# output.net
KiCad netlist of a schematic drawn in Altium Designer
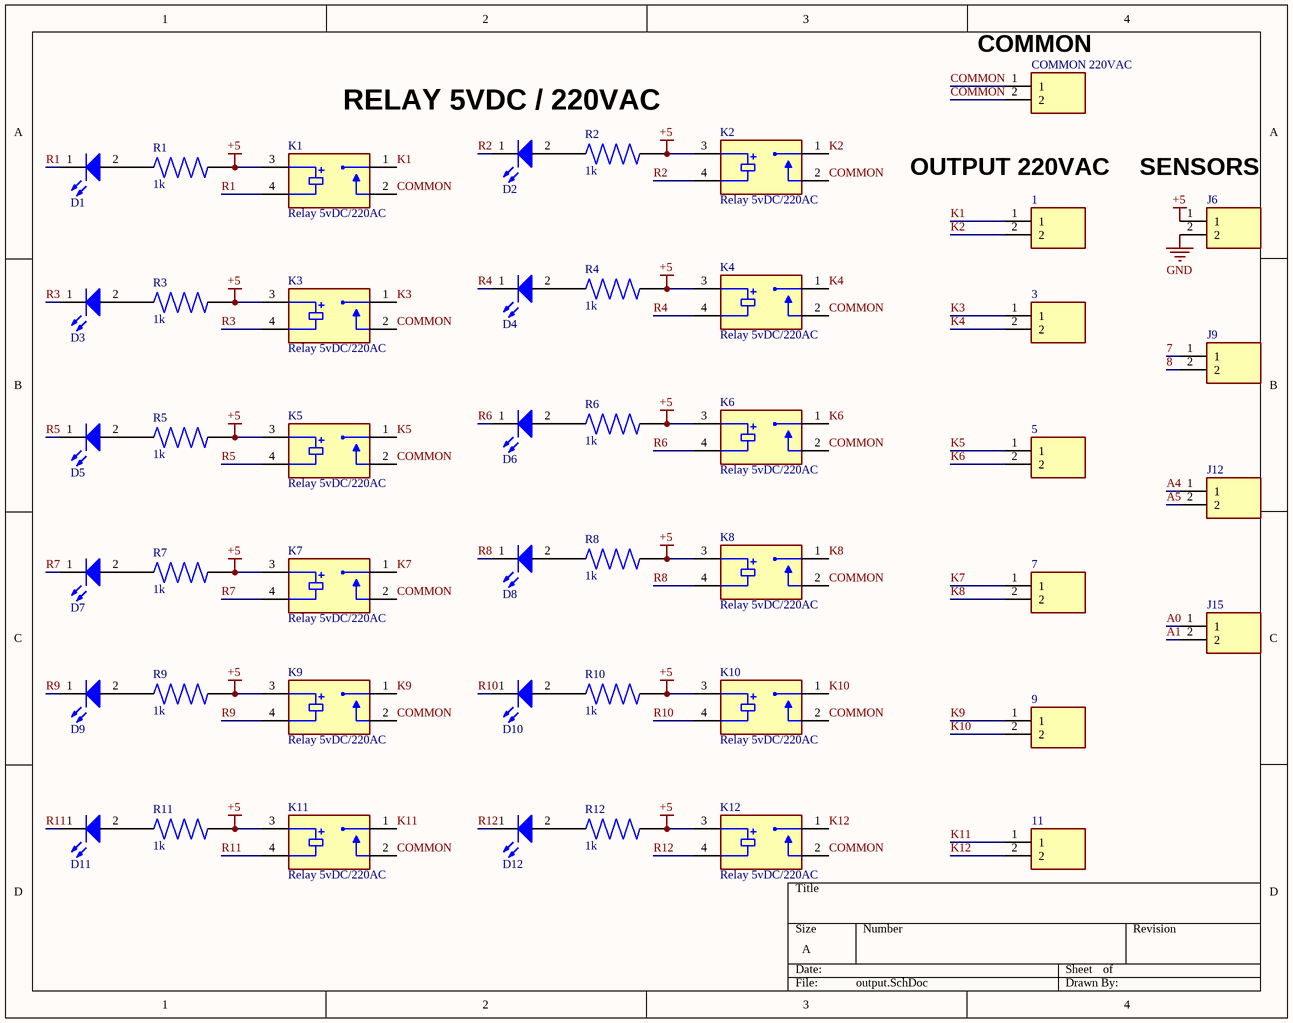
[diagram p0: output.SchDoc]

(export (version "E")
  (design (tool "Eeschema 10.0.6"))
  (components
    (comp (ref "1")
      (value "282856-2")
      (footprint "TE_282856-2")
      (description "TERMI-BLOK PCB MOUNT 2P")
      (fields (field (name "MF") "TE Connectivity"))
      (libsource (lib "input") (part "282856-2"))
    )
    (comp (ref "3")
      (value "282856-2")
      (footprint "TE_282856-2")
      (description "TERMI-BLOK PCB MOUNT 2P")
      (fields (field (name "MF") "TE Connectivity"))
      (libsource (lib "input") (part "282856-2"))
    )
    (comp (ref "5")
      (value "282856-2")
      (footprint "TE_282856-2")
      (description "TERMI-BLOK PCB MOUNT 2P")
      (fields (field (name "MF") "TE Connectivity"))
      (libsource (lib "input") (part "282856-2"))
    )
    (comp (ref "7")
      (value "282856-2")
      (footprint "TE_282856-2")
      (description "TERMI-BLOK PCB MOUNT 2P")
      (fields (field (name "MF") "TE Connectivity"))
      (libsource (lib "input") (part "282856-2"))
    )
    (comp (ref "9")
      (value "282856-2")
      (footprint "TE_282856-2")
      (description "TERMI-BLOK PCB MOUNT 2P")
      (fields (field (name "MF") "TE Connectivity"))
      (libsource (lib "input") (part "282856-2"))
    )
    (comp (ref "11")
      (value "282856-2")
      (footprint "TE_282856-2")
      (description "TERMI-BLOK PCB MOUNT 2P")
      (fields (field (name "MF") "TE Connectivity"))
      (libsource (lib "input") (part "282856-2"))
    )
    (comp (ref "COMMON 220VAC")
      (value "282856-2")
      (footprint "TE_282856-2")
      (description "TERMI-BLOK PCB MOUNT 2P")
      (fields (field (name "MF") "TE Connectivity"))
      (libsource (lib "input") (part "282856-2"))
    )
    (comp (ref "D1")
      (value "Infrared, 1.4V, 140°")
      (footprint "WL-SICW_0805_L2W1.3H0.8")
      (description "WL-SICW SMT Chip LED Infrared Waterclear, size 1206, Infrared, 1.4V, 140°")
      (fields
        (field (name "MANUFACTURER PART NUMBER") "15412085BA400")
        (field (name "MANUFACTURER") "Wurth Elektronik")
      )
      (libsource (lib "input") (part "15412085BA400"))
    )
    (comp (ref "D2")
      (value "Infrared, 1.4V, 140°")
      (footprint "WL-SICW_0805_L2W1.3H0.8")
      (description "WL-SICW SMT Chip LED Infrared Waterclear, size 1206, Infrared, 1.4V, 140°")
      (fields
        (field (name "MANUFACTURER PART NUMBER") "15412085BA400")
        (field (name "MANUFACTURER") "Wurth Elektronik")
      )
      (libsource (lib "input") (part "15412085BA400"))
    )
    (comp (ref "D3")
      (value "Infrared, 1.4V, 140°")
      (footprint "WL-SICW_0805_L2W1.3H0.8")
      (description "WL-SICW SMT Chip LED Infrared Waterclear, size 1206, Infrared, 1.4V, 140°")
      (fields
        (field (name "MANUFACTURER PART NUMBER") "15412085BA400")
        (field (name "MANUFACTURER") "Wurth Elektronik")
      )
      (libsource (lib "input") (part "15412085BA400"))
    )
    (comp (ref "D4")
      (value "Infrared, 1.4V, 140°")
      (footprint "WL-SICW_0805_L2W1.3H0.8")
      (description "WL-SICW SMT Chip LED Infrared Waterclear, size 1206, Infrared, 1.4V, 140°")
      (fields
        (field (name "MANUFACTURER PART NUMBER") "15412085BA400")
        (field (name "MANUFACTURER") "Wurth Elektronik")
      )
      (libsource (lib "input") (part "15412085BA400"))
    )
    (comp (ref "D5")
      (value "Infrared, 1.4V, 140°")
      (footprint "WL-SICW_0805_L2W1.3H0.8")
      (description "WL-SICW SMT Chip LED Infrared Waterclear, size 1206, Infrared, 1.4V, 140°")
      (fields
        (field (name "MANUFACTURER PART NUMBER") "15412085BA400")
        (field (name "MANUFACTURER") "Wurth Elektronik")
      )
      (libsource (lib "input") (part "15412085BA400"))
    )
    (comp (ref "D6")
      (value "Infrared, 1.4V, 140°")
      (footprint "WL-SICW_0805_L2W1.3H0.8")
      (description "WL-SICW SMT Chip LED Infrared Waterclear, size 1206, Infrared, 1.4V, 140°")
      (fields
        (field (name "MANUFACTURER PART NUMBER") "15412085BA400")
        (field (name "MANUFACTURER") "Wurth Elektronik")
      )
      (libsource (lib "input") (part "15412085BA400"))
    )
    (comp (ref "D7")
      (value "Infrared, 1.4V, 140°")
      (footprint "WL-SICW_0805_L2W1.3H0.8")
      (description "WL-SICW SMT Chip LED Infrared Waterclear, size 1206, Infrared, 1.4V, 140°")
      (fields
        (field (name "MANUFACTURER PART NUMBER") "15412085BA400")
        (field (name "MANUFACTURER") "Wurth Elektronik")
      )
      (libsource (lib "input") (part "15412085BA400"))
    )
    (comp (ref "D8")
      (value "Infrared, 1.4V, 140°")
      (footprint "WL-SICW_0805_L2W1.3H0.8")
      (description "WL-SICW SMT Chip LED Infrared Waterclear, size 1206, Infrared, 1.4V, 140°")
      (fields
        (field (name "MANUFACTURER PART NUMBER") "15412085BA400")
        (field (name "MANUFACTURER") "Wurth Elektronik")
      )
      (libsource (lib "input") (part "15412085BA400"))
    )
    (comp (ref "D9")
      (value "Infrared, 1.4V, 140°")
      (footprint "WL-SICW_0805_L2W1.3H0.8")
      (description "WL-SICW SMT Chip LED Infrared Waterclear, size 1206, Infrared, 1.4V, 140°")
      (fields
        (field (name "MANUFACTURER PART NUMBER") "15412085BA400")
        (field (name "MANUFACTURER") "Wurth Elektronik")
      )
      (libsource (lib "input") (part "15412085BA400"))
    )
    (comp (ref "D10")
      (value "Infrared, 1.4V, 140°")
      (footprint "WL-SICW_0805_L2W1.3H0.8")
      (description "WL-SICW SMT Chip LED Infrared Waterclear, size 1206, Infrared, 1.4V, 140°")
      (fields
        (field (name "MANUFACTURER PART NUMBER") "15412085BA400")
        (field (name "MANUFACTURER") "Wurth Elektronik")
      )
      (libsource (lib "input") (part "15412085BA400"))
    )
    (comp (ref "D11")
      (value "Infrared, 1.4V, 140°")
      (footprint "WL-SICW_0805_L2W1.3H0.8")
      (description "WL-SICW SMT Chip LED Infrared Waterclear, size 1206, Infrared, 1.4V, 140°")
      (fields
        (field (name "MANUFACTURER PART NUMBER") "15412085BA400")
        (field (name "MANUFACTURER") "Wurth Elektronik")
      )
      (libsource (lib "input") (part "15412085BA400"))
    )
    (comp (ref "D12")
      (value "Infrared, 1.4V, 140°")
      (footprint "WL-SICW_0805_L2W1.3H0.8")
      (description "WL-SICW SMT Chip LED Infrared Waterclear, size 1206, Infrared, 1.4V, 140°")
      (fields
        (field (name "MANUFACTURER PART NUMBER") "15412085BA400")
        (field (name "MANUFACTURER") "Wurth Elektronik")
      )
      (libsource (lib "input") (part "15412085BA400"))
    )
    (comp (ref "J6")
      (value "282856-2")
      (footprint "TE_282856-2")
      (description "TERMI-BLOK PCB MOUNT 2P")
      (fields (field (name "MF") "TE Connectivity"))
      (libsource (lib "input") (part "282856-2"))
    )
    (comp (ref "J9")
      (value "282856-2")
      (footprint "TE_282856-2")
      (description "TERMI-BLOK PCB MOUNT 2P")
      (fields (field (name "MF") "TE Connectivity"))
      (libsource (lib "input") (part "282856-2"))
    )
    (comp (ref "J12")
      (value "282856-2")
      (footprint "TE_282856-2")
      (description "TERMI-BLOK PCB MOUNT 2P")
      (fields (field (name "MF") "TE Connectivity"))
      (libsource (lib "input") (part "282856-2"))
    )
    (comp (ref "J15")
      (value "282856-2")
      (footprint "TE_282856-2")
      (description "TERMI-BLOK PCB MOUNT 2P")
      (fields (field (name "MF") "TE Connectivity"))
      (libsource (lib "input") (part "282856-2"))
    )
    (comp (ref "K1")
      (value "Relay 5vDC/220AC")
      (footprint "control:RELAY_G3MB-202PDC5")
      (description "Solid State SPST-NO (1 Form A) 4-SIP")
      (fields (field (name "MP") "G3MB-202P DC5") (field (name "MF") "Omron Automation"))
      (libsource (lib "control") (part "G3MB-202PDC5"))
    )
    (comp (ref "K2")
      (value "Relay 5vDC/220AC")
      (footprint "control:RELAY_G3MB-202PDC5")
      (description "Solid State SPST-NO (1 Form A) 4-SIP")
      (fields (field (name "MP") "G3MB-202P DC5") (field (name "MF") "Omron Automation"))
      (libsource (lib "control") (part "G3MB-202PDC5"))
    )
    (comp (ref "K3")
      (value "Relay 5vDC/220AC")
      (footprint "control:RELAY_G3MB-202PDC5")
      (description "Solid State SPST-NO (1 Form A) 4-SIP")
      (fields (field (name "MP") "G3MB-202P DC5") (field (name "MF") "Omron Automation"))
      (libsource (lib "control") (part "G3MB-202PDC5"))
    )
    (comp (ref "K4")
      (value "Relay 5vDC/220AC")
      (footprint "control:RELAY_G3MB-202PDC5")
      (description "Solid State SPST-NO (1 Form A) 4-SIP")
      (fields (field (name "MP") "G3MB-202P DC5") (field (name "MF") "Omron Automation"))
      (libsource (lib "control") (part "G3MB-202PDC5"))
    )
    (comp (ref "K5")
      (value "Relay 5vDC/220AC")
      (footprint "control:RELAY_G3MB-202PDC5")
      (description "Solid State SPST-NO (1 Form A) 4-SIP")
      (fields (field (name "MP") "G3MB-202P DC5") (field (name "MF") "Omron Automation"))
      (libsource (lib "control") (part "G3MB-202PDC5"))
    )
    (comp (ref "K6")
      (value "Relay 5vDC/220AC")
      (footprint "control:RELAY_G3MB-202PDC5")
      (description "Solid State SPST-NO (1 Form A) 4-SIP")
      (fields (field (name "MP") "G3MB-202P DC5") (field (name "MF") "Omron Automation"))
      (libsource (lib "control") (part "G3MB-202PDC5"))
    )
    (comp (ref "K7")
      (value "Relay 5vDC/220AC")
      (footprint "control:RELAY_G3MB-202PDC5")
      (description "Solid State SPST-NO (1 Form A) 4-SIP")
      (fields (field (name "MP") "G3MB-202P DC5") (field (name "MF") "Omron Automation"))
      (libsource (lib "control") (part "G3MB-202PDC5"))
    )
    (comp (ref "K8")
      (value "Relay 5vDC/220AC")
      (footprint "control:RELAY_G3MB-202PDC5")
      (description "Solid State SPST-NO (1 Form A) 4-SIP")
      (fields (field (name "MP") "G3MB-202P DC5") (field (name "MF") "Omron Automation"))
      (libsource (lib "control") (part "G3MB-202PDC5"))
    )
    (comp (ref "K9")
      (value "Relay 5vDC/220AC")
      (footprint "control:RELAY_G3MB-202PDC5")
      (description "Solid State SPST-NO (1 Form A) 4-SIP")
      (fields (field (name "MP") "G3MB-202P DC5") (field (name "MF") "Omron Automation"))
      (libsource (lib "control") (part "G3MB-202PDC5"))
    )
    (comp (ref "K10")
      (value "Relay 5vDC/220AC")
      (footprint "control:RELAY_G3MB-202PDC5")
      (description "Solid State SPST-NO (1 Form A) 4-SIP")
      (fields (field (name "MP") "G3MB-202P DC5") (field (name "MF") "Omron Automation"))
      (libsource (lib "control") (part "G3MB-202PDC5"))
    )
    (comp (ref "K11")
      (value "Relay 5vDC/220AC")
      (footprint "control:RELAY_G3MB-202PDC5")
      (description "Solid State SPST-NO (1 Form A) 4-SIP")
      (fields (field (name "MP") "G3MB-202P DC5") (field (name "MF") "Omron Automation"))
      (libsource (lib "control") (part "G3MB-202PDC5"))
    )
    (comp (ref "K12")
      (value "Relay 5vDC/220AC")
      (footprint "control:RELAY_G3MB-202PDC5")
      (description "Solid State SPST-NO (1 Form A) 4-SIP")
      (fields (field (name "MP") "G3MB-202P DC5") (field (name "MF") "Omron Automation"))
      (libsource (lib "control") (part "G3MB-202PDC5"))
    )
    (comp (ref "R1")
      (value "1k")
      (footprint "RESC3216X70N")
      (description "Res 1206 10 Ohm 5% 1/8W Â±500ppm/Â°C Molded SMD SMD T/R")
      (fields (field (name "TOLERANCE") "5%") (field (name "MP") "FCR1206J10R"))
      (libsource (lib "input") (part "FCR1206J10R"))
    )
    (comp (ref "R2")
      (value "1k")
      (footprint "RESC3216X70N")
      (description "Res 1206 10 Ohm 5% 1/8W Â±500ppm/Â°C Molded SMD SMD T/R")
      (fields (field (name "TOLERANCE") "5%") (field (name "MP") "FCR1206J10R"))
      (libsource (lib "input") (part "FCR1206J10R"))
    )
    (comp (ref "R3")
      (value "1k")
      (footprint "RESC3216X70N")
      (description "Res 1206 10 Ohm 5% 1/8W Â±500ppm/Â°C Molded SMD SMD T/R")
      (fields (field (name "TOLERANCE") "5%") (field (name "MP") "FCR1206J10R"))
      (libsource (lib "input") (part "FCR1206J10R"))
    )
    (comp (ref "R4")
      (value "1k")
      (footprint "RESC3216X70N")
      (description "Res 1206 10 Ohm 5% 1/8W Â±500ppm/Â°C Molded SMD SMD T/R")
      (fields (field (name "TOLERANCE") "5%") (field (name "MP") "FCR1206J10R"))
      (libsource (lib "input") (part "FCR1206J10R"))
    )
    (comp (ref "R5")
      (value "1k")
      (footprint "RESC3216X70N")
      (description "Res 1206 10 Ohm 5% 1/8W Â±500ppm/Â°C Molded SMD SMD T/R")
      (fields (field (name "TOLERANCE") "5%") (field (name "MP") "FCR1206J10R"))
      (libsource (lib "input") (part "FCR1206J10R"))
    )
    (comp (ref "R6")
      (value "1k")
      (footprint "RESC3216X70N")
      (description "Res 1206 10 Ohm 5% 1/8W Â±500ppm/Â°C Molded SMD SMD T/R")
      (fields (field (name "TOLERANCE") "5%") (field (name "MP") "FCR1206J10R"))
      (libsource (lib "input") (part "FCR1206J10R"))
    )
    (comp (ref "R7")
      (value "1k")
      (footprint "RESC3216X70N")
      (description "Res 1206 10 Ohm 5% 1/8W Â±500ppm/Â°C Molded SMD SMD T/R")
      (fields (field (name "TOLERANCE") "5%") (field (name "MP") "FCR1206J10R"))
      (libsource (lib "input") (part "FCR1206J10R"))
    )
    (comp (ref "R8")
      (value "1k")
      (footprint "RESC3216X70N")
      (description "Res 1206 10 Ohm 5% 1/8W Â±500ppm/Â°C Molded SMD SMD T/R")
      (fields (field (name "TOLERANCE") "5%") (field (name "MP") "FCR1206J10R"))
      (libsource (lib "input") (part "FCR1206J10R"))
    )
    (comp (ref "R9")
      (value "1k")
      (footprint "RESC3216X70N")
      (description "Res 1206 10 Ohm 5% 1/8W Â±500ppm/Â°C Molded SMD SMD T/R")
      (fields (field (name "TOLERANCE") "5%") (field (name "MP") "FCR1206J10R"))
      (libsource (lib "input") (part "FCR1206J10R"))
    )
    (comp (ref "R10")
      (value "1k")
      (footprint "RESC3216X70N")
      (description "Res 1206 10 Ohm 5% 1/8W Â±500ppm/Â°C Molded SMD SMD T/R")
      (fields (field (name "TOLERANCE") "5%") (field (name "MP") "FCR1206J10R"))
      (libsource (lib "input") (part "FCR1206J10R"))
    )
    (comp (ref "R11")
      (value "1k")
      (footprint "RESC3216X70N")
      (description "Res 1206 10 Ohm 5% 1/8W Â±500ppm/Â°C Molded SMD SMD T/R")
      (fields (field (name "TOLERANCE") "5%") (field (name "MP") "FCR1206J10R"))
      (libsource (lib "input") (part "FCR1206J10R"))
    )
    (comp (ref "R12")
      (value "1k")
      (footprint "RESC3216X70N")
      (description "Res 1206 10 Ohm 5% 1/8W Â±500ppm/Â°C Molded SMD SMD T/R")
      (fields (field (name "TOLERANCE") "5%") (field (name "MP") "FCR1206J10R"))
      (libsource (lib "input") (part "FCR1206J10R"))
    )
  )
  (nets
    (net (code "1") (name "+5") (class "Default")
      (node (ref "J6") (pin "1") (pinfunction "1_1") (pintype "passive"))
      (node (ref "K1") (pin "3") (pinfunction "3_3") (pintype "passive"))
      (node (ref "K10") (pin "3") (pinfunction "3_3") (pintype "passive"))
      (node (ref "K11") (pin "3") (pinfunction "3_3") (pintype "passive"))
      (node (ref "K12") (pin "3") (pinfunction "3_3") (pintype "passive"))
      (node (ref "K2") (pin "3") (pinfunction "3_3") (pintype "passive"))
      (node (ref "K3") (pin "3") (pinfunction "3_3") (pintype "passive"))
      (node (ref "K4") (pin "3") (pinfunction "3_3") (pintype "passive"))
      (node (ref "K5") (pin "3") (pinfunction "3_3") (pintype "passive"))
      (node (ref "K6") (pin "3") (pinfunction "3_3") (pintype "passive"))
      (node (ref "K7") (pin "3") (pinfunction "3_3") (pintype "passive"))
      (node (ref "K8") (pin "3") (pinfunction "3_3") (pintype "passive"))
      (node (ref "K9") (pin "3") (pinfunction "3_3") (pintype "passive"))
      (node (ref "R1") (pin "2") (pinfunction "2_2") (pintype "passive"))
      (node (ref "R10") (pin "2") (pinfunction "2_2") (pintype "passive"))
      (node (ref "R11") (pin "2") (pinfunction "2_2") (pintype "passive"))
      (node (ref "R12") (pin "2") (pinfunction "2_2") (pintype "passive"))
      (node (ref "R2") (pin "2") (pinfunction "2_2") (pintype "passive"))
      (node (ref "R3") (pin "2") (pinfunction "2_2") (pintype "passive"))
      (node (ref "R4") (pin "2") (pinfunction "2_2") (pintype "passive"))
      (node (ref "R5") (pin "2") (pinfunction "2_2") (pintype "passive"))
      (node (ref "R6") (pin "2") (pinfunction "2_2") (pintype "passive"))
      (node (ref "R7") (pin "2") (pinfunction "2_2") (pintype "passive"))
      (node (ref "R8") (pin "2") (pinfunction "2_2") (pintype "passive"))
      (node (ref "R9") (pin "2") (pinfunction "2_2") (pintype "passive"))
    )
    (net (code "2") (name "/7") (class "Default")
      (node (ref "J9") (pin "1") (pinfunction "1_1") (pintype "passive"))
    )
    (net (code "3") (name "/8") (class "Default")
      (node (ref "J9") (pin "2") (pinfunction "2_2") (pintype "passive"))
    )
    (net (code "5") (name "/A0") (class "Default")
      (node (ref "J15") (pin "1") (pinfunction "1_1") (pintype "passive"))
    )
    (net (code "6") (name "/A1") (class "Default")
      (node (ref "J15") (pin "2") (pinfunction "2_2") (pintype "passive"))
    )
    (net (code "7") (name "/A4") (class "Default")
      (node (ref "J12") (pin "1") (pinfunction "1_1") (pintype "passive"))
    )
    (net (code "8") (name "/A5") (class "Default")
      (node (ref "J12") (pin "2") (pinfunction "2_2") (pintype "passive"))
    )
    (net (code "9") (name "/COMMON") (class "Default")
      (node (ref "COMMON 220VAC") (pin "1") (pinfunction "1_1") (pintype "passive"))
      (node (ref "COMMON 220VAC") (pin "2") (pinfunction "2_2") (pintype "passive"))
      (node (ref "K1") (pin "2") (pinfunction "2_2") (pintype "passive"))
      (node (ref "K10") (pin "2") (pinfunction "2_2") (pintype "passive"))
      (node (ref "K11") (pin "2") (pinfunction "2_2") (pintype "passive"))
      (node (ref "K12") (pin "2") (pinfunction "2_2") (pintype "passive"))
      (node (ref "K2") (pin "2") (pinfunction "2_2") (pintype "passive"))
      (node (ref "K3") (pin "2") (pinfunction "2_2") (pintype "passive"))
      (node (ref "K4") (pin "2") (pinfunction "2_2") (pintype "passive"))
      (node (ref "K5") (pin "2") (pinfunction "2_2") (pintype "passive"))
      (node (ref "K6") (pin "2") (pinfunction "2_2") (pintype "passive"))
      (node (ref "K7") (pin "2") (pinfunction "2_2") (pintype "passive"))
      (node (ref "K8") (pin "2") (pinfunction "2_2") (pintype "passive"))
      (node (ref "K9") (pin "2") (pinfunction "2_2") (pintype "passive"))
    )
    (net (code "10") (name "/K1") (class "Default")
      (node (ref "1") (pin "1") (pinfunction "1_1") (pintype "passive"))
      (node (ref "K1") (pin "1") (pinfunction "1_1") (pintype "passive"))
    )
    (net (code "11") (name "/K2") (class "Default")
      (node (ref "1") (pin "2") (pinfunction "2_2") (pintype "passive"))
      (node (ref "K2") (pin "1") (pinfunction "1_1") (pintype "passive"))
    )
    (net (code "12") (name "/K3") (class "Default")
      (node (ref "3") (pin "1") (pinfunction "1_1") (pintype "passive"))
      (node (ref "K3") (pin "1") (pinfunction "1_1") (pintype "passive"))
    )
    (net (code "13") (name "/K4") (class "Default")
      (node (ref "3") (pin "2") (pinfunction "2_2") (pintype "passive"))
      (node (ref "K4") (pin "1") (pinfunction "1_1") (pintype "passive"))
    )
    (net (code "14") (name "/K5") (class "Default")
      (node (ref "5") (pin "1") (pinfunction "1_1") (pintype "passive"))
      (node (ref "K5") (pin "1") (pinfunction "1_1") (pintype "passive"))
    )
    (net (code "15") (name "/K6") (class "Default")
      (node (ref "5") (pin "2") (pinfunction "2_2") (pintype "passive"))
      (node (ref "K6") (pin "1") (pinfunction "1_1") (pintype "passive"))
    )
    (net (code "16") (name "/K7") (class "Default")
      (node (ref "7") (pin "1") (pinfunction "1_1") (pintype "passive"))
      (node (ref "K7") (pin "1") (pinfunction "1_1") (pintype "passive"))
    )
    (net (code "17") (name "/K8") (class "Default")
      (node (ref "7") (pin "2") (pinfunction "2_2") (pintype "passive"))
      (node (ref "K8") (pin "1") (pinfunction "1_1") (pintype "passive"))
    )
    (net (code "18") (name "/K9") (class "Default")
      (node (ref "9") (pin "1") (pinfunction "1_1") (pintype "passive"))
      (node (ref "K9") (pin "1") (pinfunction "1_1") (pintype "passive"))
    )
    (net (code "19") (name "/K10") (class "Default")
      (node (ref "9") (pin "2") (pinfunction "2_2") (pintype "passive"))
      (node (ref "K10") (pin "1") (pinfunction "1_1") (pintype "passive"))
    )
    (net (code "20") (name "/K11") (class "Default")
      (node (ref "11") (pin "1") (pinfunction "1_1") (pintype "passive"))
      (node (ref "K11") (pin "1") (pinfunction "1_1") (pintype "passive"))
    )
    (net (code "21") (name "/K12") (class "Default")
      (node (ref "11") (pin "2") (pinfunction "2_2") (pintype "passive"))
      (node (ref "K12") (pin "1") (pinfunction "1_1") (pintype "passive"))
    )
    (net (code "22") (name "/R1") (class "Default")
      (node (ref "D1") (pin "1") (pinfunction "K_1") (pintype "passive"))
      (node (ref "K1") (pin "4") (pinfunction "4_4") (pintype "passive"))
    )
    (net (code "23") (name "/R2") (class "Default")
      (node (ref "D2") (pin "1") (pinfunction "K_1") (pintype "passive"))
      (node (ref "K2") (pin "4") (pinfunction "4_4") (pintype "passive"))
    )
    (net (code "24") (name "/R3") (class "Default")
      (node (ref "D3") (pin "1") (pinfunction "K_1") (pintype "passive"))
      (node (ref "K3") (pin "4") (pinfunction "4_4") (pintype "passive"))
    )
    (net (code "25") (name "/R4") (class "Default")
      (node (ref "D4") (pin "1") (pinfunction "K_1") (pintype "passive"))
      (node (ref "K4") (pin "4") (pinfunction "4_4") (pintype "passive"))
    )
    (net (code "26") (name "/R5") (class "Default")
      (node (ref "D5") (pin "1") (pinfunction "K_1") (pintype "passive"))
      (node (ref "K5") (pin "4") (pinfunction "4_4") (pintype "passive"))
    )
    (net (code "27") (name "/R6") (class "Default")
      (node (ref "D6") (pin "1") (pinfunction "K_1") (pintype "passive"))
      (node (ref "K6") (pin "4") (pinfunction "4_4") (pintype "passive"))
    )
    (net (code "28") (name "/R7") (class "Default")
      (node (ref "D7") (pin "1") (pinfunction "K_1") (pintype "passive"))
      (node (ref "K7") (pin "4") (pinfunction "4_4") (pintype "passive"))
    )
    (net (code "29") (name "/R8") (class "Default")
      (node (ref "D8") (pin "1") (pinfunction "K_1") (pintype "passive"))
      (node (ref "K8") (pin "4") (pinfunction "4_4") (pintype "passive"))
    )
    (net (code "30") (name "/R9") (class "Default")
      (node (ref "D9") (pin "1") (pinfunction "K_1") (pintype "passive"))
      (node (ref "K9") (pin "4") (pinfunction "4_4") (pintype "passive"))
    )
    (net (code "31") (name "/R10") (class "Default")
      (node (ref "D10") (pin "1") (pinfunction "K_1") (pintype "passive"))
      (node (ref "K10") (pin "4") (pinfunction "4_4") (pintype "passive"))
    )
    (net (code "32") (name "/R11") (class "Default")
      (node (ref "D11") (pin "1") (pinfunction "K_1") (pintype "passive"))
      (node (ref "K11") (pin "4") (pinfunction "4_4") (pintype "passive"))
    )
    (net (code "33") (name "/R12") (class "Default")
      (node (ref "D12") (pin "1") (pinfunction "K_1") (pintype "passive"))
      (node (ref "K12") (pin "4") (pinfunction "4_4") (pintype "passive"))
    )
    (net (code "34") (name "GND") (class "Default")
      (node (ref "J6") (pin "2") (pinfunction "2_2") (pintype "passive"))
    )
    (net (code "35") (name "Net-(D1-A)") (class "Default")
      (node (ref "D1") (pin "2") (pinfunction "A_2") (pintype "passive"))
      (node (ref "R1") (pin "1") (pinfunction "1_1") (pintype "passive"))
    )
    (net (code "36") (name "Net-(D2-A)") (class "Default")
      (node (ref "D2") (pin "2") (pinfunction "A_2") (pintype "passive"))
      (node (ref "R2") (pin "1") (pinfunction "1_1") (pintype "passive"))
    )
    (net (code "37") (name "Net-(D3-A)") (class "Default")
      (node (ref "D3") (pin "2") (pinfunction "A_2") (pintype "passive"))
      (node (ref "R3") (pin "1") (pinfunction "1_1") (pintype "passive"))
    )
    (net (code "38") (name "Net-(D4-A)") (class "Default")
      (node (ref "D4") (pin "2") (pinfunction "A_2") (pintype "passive"))
      (node (ref "R4") (pin "1") (pinfunction "1_1") (pintype "passive"))
    )
    (net (code "39") (name "Net-(D5-A)") (class "Default")
      (node (ref "D5") (pin "2") (pinfunction "A_2") (pintype "passive"))
      (node (ref "R5") (pin "1") (pinfunction "1_1") (pintype "passive"))
    )
    (net (code "40") (name "Net-(D6-A)") (class "Default")
      (node (ref "D6") (pin "2") (pinfunction "A_2") (pintype "passive"))
      (node (ref "R6") (pin "1") (pinfunction "1_1") (pintype "passive"))
    )
    (net (code "41") (name "Net-(D7-A)") (class "Default")
      (node (ref "D7") (pin "2") (pinfunction "A_2") (pintype "passive"))
      (node (ref "R7") (pin "1") (pinfunction "1_1") (pintype "passive"))
    )
    (net (code "42") (name "Net-(D8-A)") (class "Default")
      (node (ref "D8") (pin "2") (pinfunction "A_2") (pintype "passive"))
      (node (ref "R8") (pin "1") (pinfunction "1_1") (pintype "passive"))
    )
    (net (code "43") (name "Net-(D9-A)") (class "Default")
      (node (ref "D9") (pin "2") (pinfunction "A_2") (pintype "passive"))
      (node (ref "R9") (pin "1") (pinfunction "1_1") (pintype "passive"))
    )
    (net (code "44") (name "Net-(D10-A)") (class "Default")
      (node (ref "D10") (pin "2") (pinfunction "A_2") (pintype "passive"))
      (node (ref "R10") (pin "1") (pinfunction "1_1") (pintype "passive"))
    )
    (net (code "45") (name "Net-(D11-A)") (class "Default")
      (node (ref "D11") (pin "2") (pinfunction "A_2") (pintype "passive"))
      (node (ref "R11") (pin "1") (pinfunction "1_1") (pintype "passive"))
    )
    (net (code "46") (name "Net-(D12-A)") (class "Default")
      (node (ref "D12") (pin "2") (pinfunction "A_2") (pintype "passive"))
      (node (ref "R12") (pin "1") (pinfunction "1_1") (pintype "passive"))
    )
  )
)
